# 4__Connectors___IO.net
KiCad netlist of a schematic drawn in Altium Designer
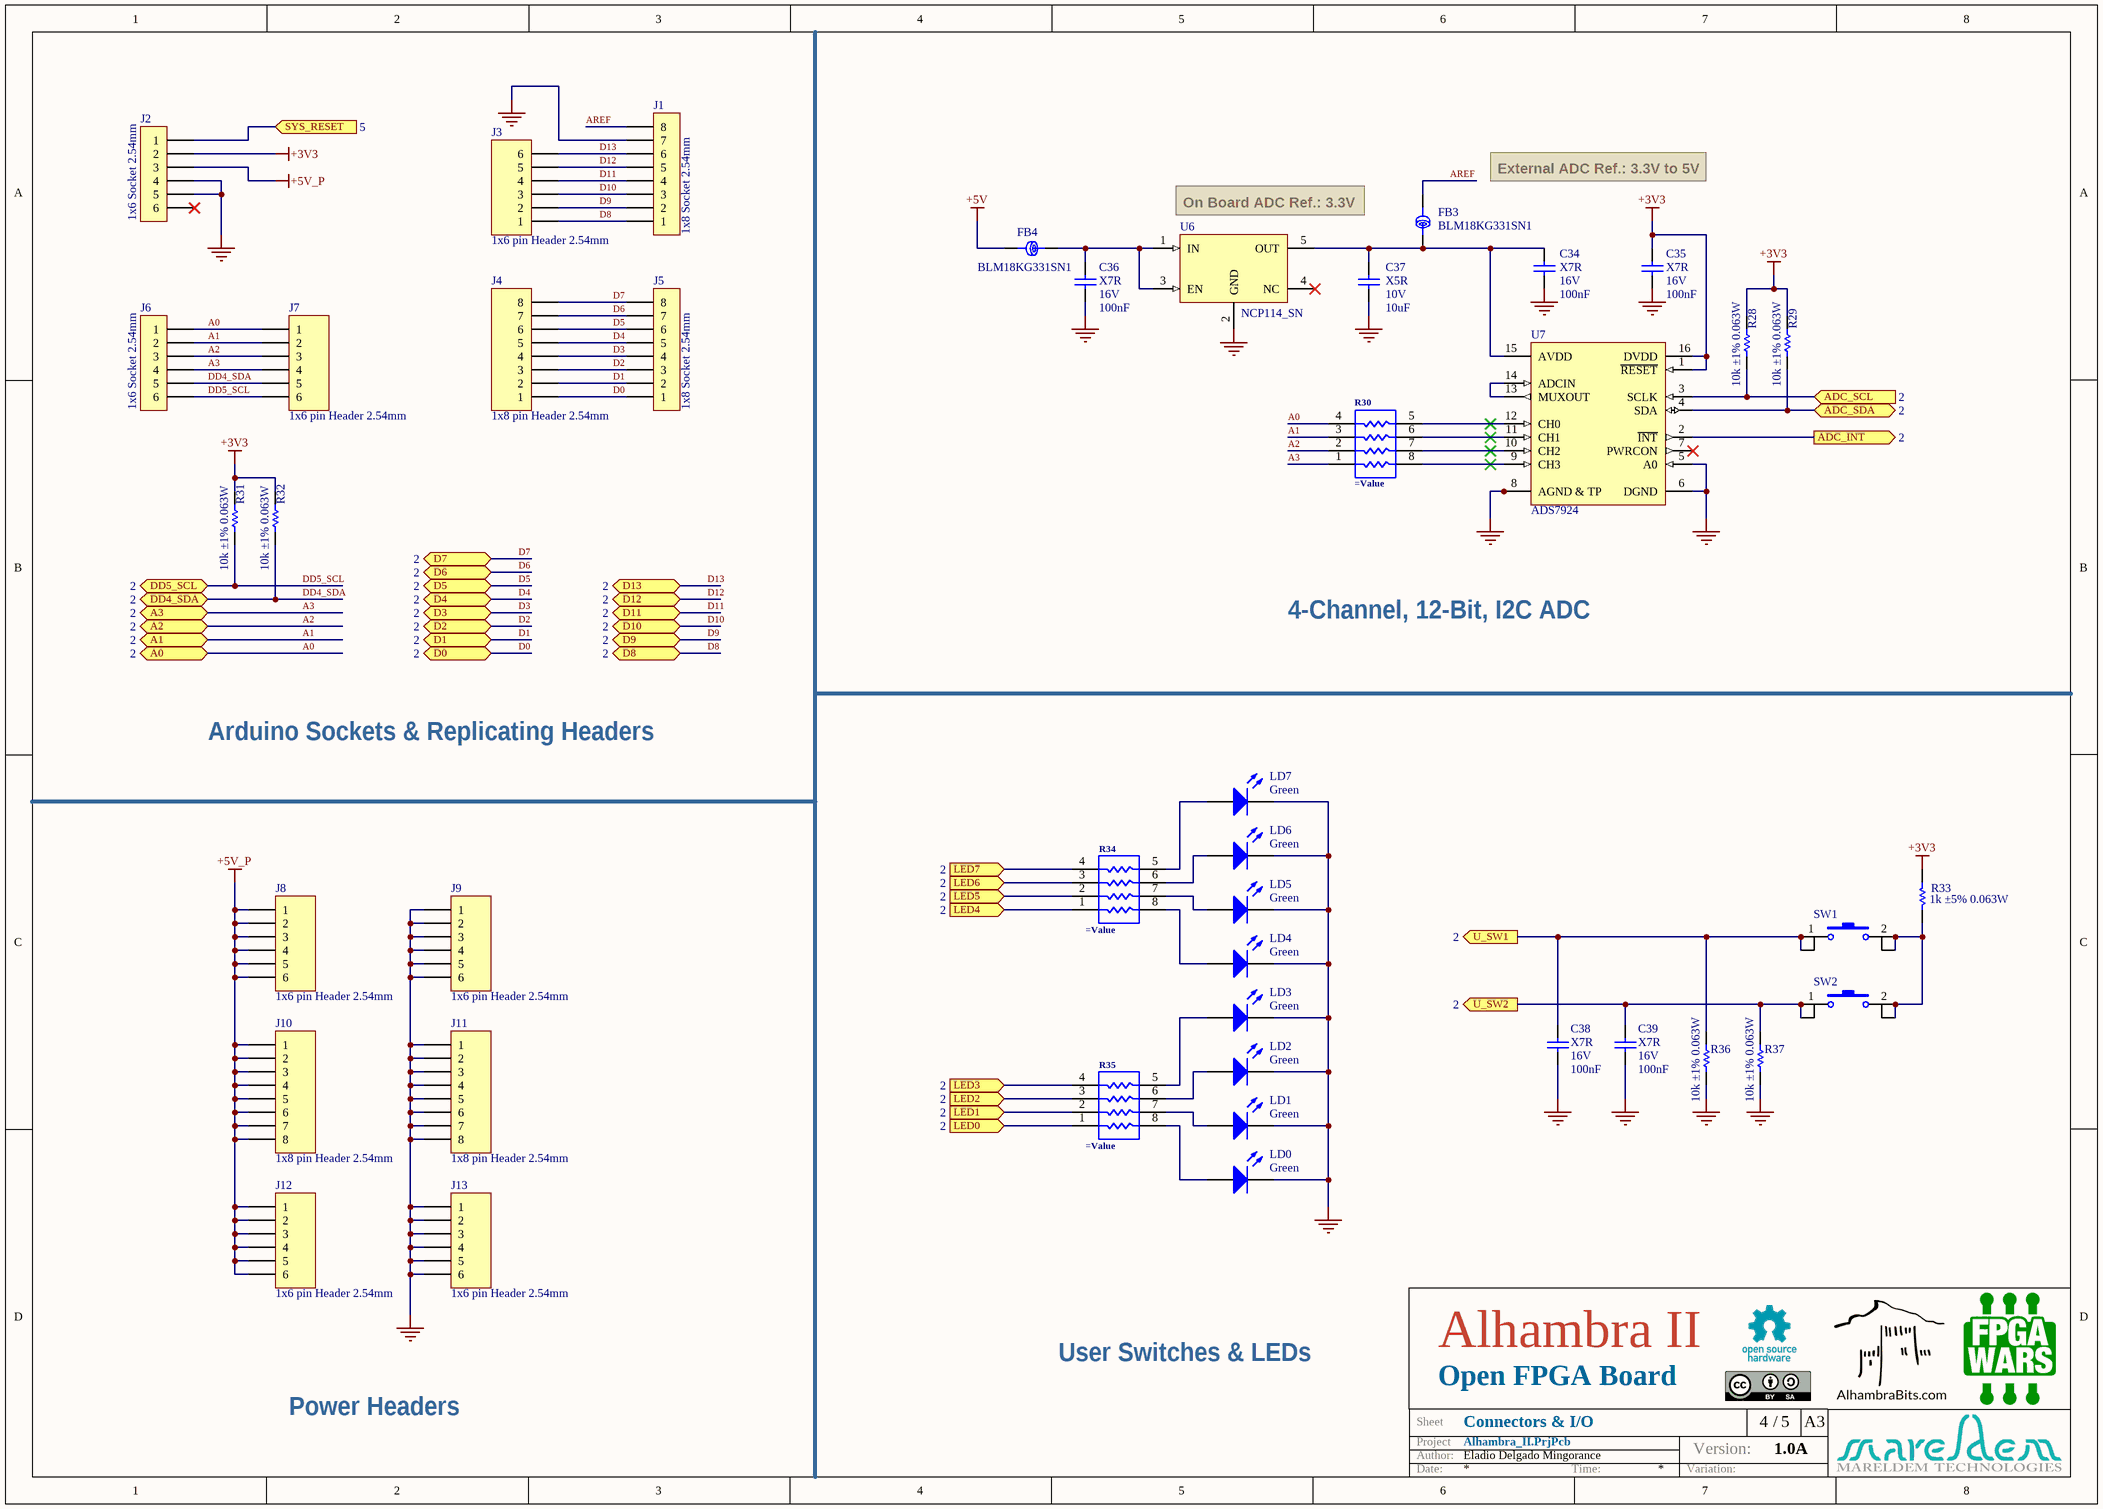
[diagram p0: [4]_Connectors_&_IO.SchDoc]

(export (version "E")
  (design (tool "Eeschema 10.0.6"))
  (components
    (comp (ref "C34")
      (value "Capacitor")
      (footprint "C0402")
      (description "Capacitor SMD")
      (fields
        (field (name "DIELECTRIC") "X7R")
        (field (name "VOLTAGE") "16V")
        (field (name "CAPACITANCE") "100nF")
        (field (name "PART NUMBER") "C0402_100nF_16V_±10%")
        (field (name "TOLERANCE") "±10%")
      )
      (libsource (lib "") (part "Capacitor_1"))
    )
    (comp (ref "C35")
      (value "Capacitor")
      (footprint "C0402")
      (description "Capacitor SMD")
      (fields
        (field (name "DIELECTRIC") "X7R")
        (field (name "VOLTAGE") "16V")
        (field (name "CAPACITANCE") "100nF")
        (field (name "PART NUMBER") "C0402_100nF_16V_±10%")
        (field (name "TOLERANCE") "±10%")
      )
      (libsource (lib "") (part "Capacitor_1"))
    )
    (comp (ref "C36")
      (value "Capacitor")
      (footprint "C0402")
      (description "Capacitor SMD")
      (fields
        (field (name "DIELECTRIC") "X7R")
        (field (name "VOLTAGE") "16V")
        (field (name "CAPACITANCE") "100nF")
        (field (name "PART NUMBER") "C0402_100nF_16V_±10%")
        (field (name "TOLERANCE") "±10%")
      )
      (libsource (lib "") (part "Capacitor_1"))
    )
    (comp (ref "C37")
      (value "Capacitor")
      (footprint "C0603")
      (description "Capacitor SMD")
      (fields
        (field (name "DIELECTRIC") "X5R")
        (field (name "VOLTAGE") "10V")
        (field (name "CAPACITANCE") "10uF")
        (field (name "PART NUMBER") "C0603_10uF_10V_±10%")
        (field (name "TOLERANCE") "±10%")
      )
      (libsource (lib "Pasives_Capacitor_SMD") (part "Capacitor"))
    )
    (comp (ref "C38")
      (value "Capacitor")
      (footprint "C0402")
      (description "Capacitor SMD")
      (fields
        (field (name "DIELECTRIC") "X7R")
        (field (name "VOLTAGE") "16V")
        (field (name "CAPACITANCE") "100nF")
        (field (name "PART NUMBER") "C0402_100nF_16V_±10%")
        (field (name "TOLERANCE") "±10%")
      )
      (libsource (lib "") (part "Capacitor_1"))
    )
    (comp (ref "C39")
      (value "Capacitor")
      (footprint "C0402")
      (description "Capacitor SMD")
      (fields
        (field (name "DIELECTRIC") "X7R")
        (field (name "VOLTAGE") "16V")
        (field (name "CAPACITANCE") "100nF")
        (field (name "PART NUMBER") "C0402_100nF_16V_±10%")
        (field (name "TOLERANCE") "±10%")
      )
      (libsource (lib "") (part "Capacitor_1"))
    )
    (comp (ref "FB3")
      (value "BLM18KG331SN1")
      (footprint "L0603")
      (description "Ferrite Bead")
      (fields (field (name "PART NUMBER") "L0603_330R_0,080R_1700 mA") (field (name "MANUFACTURER") "Murata"))
      (libsource (lib "") (part "Ferrite Bead_1"))
    )
    (comp (ref "FB4")
      (value "BLM18KG331SN1")
      (footprint "L0603")
      (description "Ferrite Bead")
      (fields (field (name "PART NUMBER") "L0603_330R_0,080R_1700 mA") (field (name "MANUFACTURER") "Murata"))
      (libsource (lib "Pasives_Inductor_SMD") (part "Ferrite Bead"))
    )
    (comp (ref "J1")
      (value "1x8 Socket 2.54mm")
      (footprint "1x8 Socket Header THT 2.54mm PIH")
      (description "Connector, 8 pin Socket Header 2.54mm")
      (fields (field (name "MANUFACTURER") "Samtec") (field (name "PART NUMBER") "CON_SH_THT2.54_8 PIH"))
      (libsource (lib "Connector_SocketHeader_2.54") (part "1x8 Socket Header 2.54mm"))
    )
    (comp (ref "J2")
      (value "1x6 Socket 2.54mm")
      (footprint "1x6 Socket Header THT 2.54mm PIH")
      (description "Connector, 6 pin Socket Header 2.54mm")
      (fields (field (name "MANUFACTURER") "Samtec") (field (name "PART NUMBER") "CON_SH_THT2.54_6 PIH"))
      (libsource (lib "Connector_SocketHeader_2.54") (part "1x6 Socket Header 2.54mm"))
    )
    (comp (ref "J3")
      (value "1x6 pin Header 2.54mm")
      (footprint "1x6 Pin Header 2.54 WHITE PIH")
      (description "Connector, 1x6 pin Header 2.54mm")
      (fields
        (field (name "MANUFACTURER") "Samtec")
        (field (name "PART NUMBER") "CON_PH_THT2.54_6 Natural PIH")
      )
      (libsource (lib "") (part "1x6 pin Header 2.54mm_1"))
    )
    (comp (ref "J4")
      (value "1x8 pin Header 2.54mm")
      (footprint "1x8 Pin Header 2.54 WHITE PIH")
      (description "Connector, 1x8 pin Header 2.54mm")
      (fields
        (field (name "MANUFACTURER") "Samtec")
        (field (name "PART NUMBER") "CON_PH_THT2.54_8 Natural PIH")
      )
      (libsource (lib "") (part "1x8 pin Header 2.54mm_1"))
    )
    (comp (ref "J5")
      (value "1x8 Socket 2.54mm")
      (footprint "1x8 Socket Header THT 2.54mm PIH")
      (description "Connector, 8 pin Socket Header 2.54mm")
      (fields (field (name "MANUFACTURER") "Samtec") (field (name "PART NUMBER") "CON_SH_THT2.54_8 PIH"))
      (libsource (lib "Connector_SocketHeader_2.54") (part "1x8 Socket Header 2.54mm"))
    )
    (comp (ref "J6")
      (value "1x6 Socket 2.54mm")
      (footprint "1x6 Socket Header THT 2.54mm PIH")
      (description "Connector, 6 pin Socket Header 2.54mm")
      (fields (field (name "MANUFACTURER") "Samtec") (field (name "PART NUMBER") "CON_SH_THT2.54_6 PIH"))
      (libsource (lib "Connector_SocketHeader_2.54") (part "1x6 Socket Header 2.54mm"))
    )
    (comp (ref "J7")
      (value "1x6 pin Header 2.54mm")
      (footprint "1x6 Pin Header 2.54 WHITE PIH")
      (description "Connector, 1x6 pin Header 2.54mm")
      (fields
        (field (name "MANUFACTURER") "Samtec")
        (field (name "PART NUMBER") "CON_PH_THT2.54_6 Natural PIH")
      )
      (libsource (lib "Connector_PinHeader_2.54") (part "1x6 pin Header 2.54mm"))
    )
    (comp (ref "J8")
      (value "1x6 pin Header 2.54mm")
      (footprint "1x6 Pin Header 2.54 RED PIH")
      (description "Connector, 1x6 pin Header 2.54mm")
      (fields (field (name "MANUFACTURER") "Samtec") (field (name "PART NUMBER") "CON_PH_THT2.54_6 Red PIH"))
      (libsource (lib "Connector_PinHeader_2.54") (part "1x6 pin Header 2.54mm"))
    )
    (comp (ref "J9")
      (value "1x6 pin Header 2.54mm")
      (footprint "1x6 Pin Header 2.54 BLACK PIH")
      (description "Connector, 1x6 pin Header 2.54mm")
      (fields
        (field (name "MANUFACTURER") "Samtec")
        (field (name "PART NUMBER") "CON_PH_THT2.54_6 Black PIH")
      )
      (libsource (lib "Connector_PinHeader_2.54") (part "1x6 pin Header 2.54mm"))
    )
    (comp (ref "J10")
      (value "1x8 pin Header 2.54mm")
      (footprint "1x8 Pin Header 2.54 RED PIH")
      (description "Connector, 1x8 pin Header 2.54mm")
      (fields (field (name "MANUFACTURER") "Samtec") (field (name "PART NUMBER") "CON_PH_THT2.54_8 Red PIH"))
      (libsource (lib "Connector_PinHeader_2.54") (part "1x8 pin Header 2.54mm"))
    )
    (comp (ref "J11")
      (value "1x8 pin Header 2.54mm")
      (footprint "1x8 Pin Header 2.54 BLACK PIH")
      (description "Connector, 1x8 pin Header 2.54mm")
      (fields
        (field (name "MANUFACTURER") "Samtec")
        (field (name "PART NUMBER") "CON_PH_THT2.54_8 Black PIH")
      )
      (libsource (lib "Connector_PinHeader_2.54") (part "1x8 pin Header 2.54mm"))
    )
    (comp (ref "J12")
      (value "1x6 pin Header 2.54mm")
      (footprint "1x6 Pin Header 2.54 RED PIH")
      (description "Connector, 1x6 pin Header 2.54mm")
      (fields (field (name "MANUFACTURER") "Samtec") (field (name "PART NUMBER") "CON_PH_THT2.54_6 Red PIH"))
      (libsource (lib "Connector_PinHeader_2.54") (part "1x6 pin Header 2.54mm"))
    )
    (comp (ref "J13")
      (value "1x6 pin Header 2.54mm")
      (footprint "1x6 Pin Header 2.54 BLACK PIH")
      (description "Connector, 1x6 pin Header 2.54mm")
      (fields
        (field (name "MANUFACTURER") "Samtec")
        (field (name "PART NUMBER") "CON_PH_THT2.54_6 Black PIH")
      )
      (libsource (lib "Connector_PinHeader_2.54") (part "1x6 pin Header 2.54mm"))
    )
    (comp (ref "LD0")
      (value "Green")
      (footprint "LED0603")
      (description "LED")
      (fields (field (name "PART NUMBER") "LED Green 0603 Wurth") (field (name "MANUFACTURER") "WE"))
      (libsource (lib "Optoelectronics") (part "LED"))
    )
    (comp (ref "LD1")
      (value "Green")
      (footprint "LED0603")
      (description "LED")
      (fields (field (name "PART NUMBER") "LED Green 0603 Wurth") (field (name "MANUFACTURER") "WE"))
      (libsource (lib "Optoelectronics") (part "LED"))
    )
    (comp (ref "LD2")
      (value "Green")
      (footprint "LED0603")
      (description "LED")
      (fields (field (name "PART NUMBER") "LED Green 0603 Wurth") (field (name "MANUFACTURER") "WE"))
      (libsource (lib "Optoelectronics") (part "LED"))
    )
    (comp (ref "LD3")
      (value "Green")
      (footprint "LED0603")
      (description "LED")
      (fields (field (name "PART NUMBER") "LED Green 0603 Wurth") (field (name "MANUFACTURER") "WE"))
      (libsource (lib "Optoelectronics") (part "LED"))
    )
    (comp (ref "LD4")
      (value "Green")
      (footprint "LED0603")
      (description "LED")
      (fields (field (name "PART NUMBER") "LED Green 0603 Wurth") (field (name "MANUFACTURER") "WE"))
      (libsource (lib "Optoelectronics") (part "LED"))
    )
    (comp (ref "LD5")
      (value "Green")
      (footprint "LED0603")
      (description "LED")
      (fields (field (name "PART NUMBER") "LED Green 0603 Wurth") (field (name "MANUFACTURER") "WE"))
      (libsource (lib "Optoelectronics") (part "LED"))
    )
    (comp (ref "LD6")
      (value "Green")
      (footprint "LED0603")
      (description "LED")
      (fields (field (name "PART NUMBER") "LED Green 0603 Wurth") (field (name "MANUFACTURER") "WE"))
      (libsource (lib "Optoelectronics") (part "LED"))
    )
    (comp (ref "LD7")
      (value "Green")
      (footprint "LED0603")
      (description "LED")
      (fields (field (name "PART NUMBER") "LED Green 0603 Wurth") (field (name "MANUFACTURER") "WE"))
      (libsource (lib "Optoelectronics") (part "LED"))
    )
    (comp (ref "R28")
      (value "10k ±1% 0.063W")
      (footprint "R0402")
      (description "Resistor, SMD")
      (fields (field (name "TOLERANCE") "±1%") (field (name "POWER") "0.063W"))
      (libsource (lib "Pasives_Resistor_SMD") (part "Resistor"))
    )
    (comp (ref "R29")
      (value "10k ±1% 0.063W")
      (footprint "R0402")
      (description "Resistor, SMD")
      (fields (field (name "TOLERANCE") "±1%") (field (name "POWER") "0.063W"))
      (libsource (lib "Pasives_Resistor_SMD") (part "Resistor"))
    )
    (comp (ref "R30")
      (value "~")
      (footprint "4xArray_1206_Convex")
      (description "Resistor, Array 4x1")
      (fields
        (field (name "PART NUMBER") "4xArray_1206_Convex_100R_0,0625W_±5%")
        (field (name "POWER") "0,0625W")
      )
      (libsource (lib "Pasives_Resistor_SMD") (part "Resistor_4x"))
    )
    (comp (ref "R31")
      (value "10k ±1% 0.063W")
      (footprint "R0402")
      (description "Resistor, SMD")
      (fields (field (name "TOLERANCE") "±1%") (field (name "POWER") "0.063W"))
      (libsource (lib "Pasives_Resistor_SMD") (part "Resistor"))
    )
    (comp (ref "R32")
      (value "10k ±1% 0.063W")
      (footprint "R0402")
      (description "Resistor, SMD")
      (fields (field (name "TOLERANCE") "±1%") (field (name "POWER") "0.063W"))
      (libsource (lib "Pasives_Resistor_SMD") (part "Resistor"))
    )
    (comp (ref "R33")
      (value "1k ±5% 0.063W")
      (footprint "R0402")
      (description "Resistor, SMD")
      (fields (field (name "TOLERANCE") "±5%") (field (name "POWER") "0.063W"))
      (libsource (lib "Pasives_Resistor_SMD") (part "Resistor"))
    )
    (comp (ref "R34")
      (value "~")
      (footprint "4xArray_1206_Convex")
      (description "Resistor, Array 4x1")
      (fields
        (field (name "PART NUMBER") "4xArray_1206_Convex_470R_0,0625W_0,05")
        (field (name "POWER") "0,0625W")
      )
      (libsource (lib "Pasives_Resistor_SMD") (part "Resistor_4x"))
    )
    (comp (ref "R35")
      (value "~")
      (footprint "4xArray_1206_Convex")
      (description "Resistor, Array 4x1")
      (fields
        (field (name "PART NUMBER") "4xArray_1206_Convex_470R_0,0625W_0,05")
        (field (name "POWER") "0,0625W")
      )
      (libsource (lib "Pasives_Resistor_SMD") (part "Resistor_4x"))
    )
    (comp (ref "R36")
      (value "10k ±1% 0.063W")
      (footprint "R0402")
      (description "Resistor, SMD")
      (fields (field (name "TOLERANCE") "±1%") (field (name "POWER") "0.063W"))
      (libsource (lib "Pasives_Resistor_SMD") (part "Resistor"))
    )
    (comp (ref "R37")
      (value "10k ±1% 0.063W")
      (footprint "R0402")
      (description "Resistor, SMD")
      (fields (field (name "TOLERANCE") "±1%") (field (name "POWER") "0.063W"))
      (libsource (lib "Pasives_Resistor_SMD") (part "Resistor"))
    )
    (comp (ref "SW1")
      (value "Switch_4P_SP_1-3_4-2")
      (footprint "4363x30458xx")
      (description "Micro miniature pushbutton surface Switch")
      (fields (field (name "PART NUMBER") "SW 4,7x3,5 mm SMD side push") (field (name "MANUFACTURER") "WE"))
      (libsource (lib "Electromechanical") (part "Switch_4P_SP_1-3_4-2"))
    )
    (comp (ref "SW2")
      (value "Switch_4P_SP_1-3_4-2")
      (footprint "4363x30458xx")
      (description "Micro miniature pushbutton surface Switch")
      (fields (field (name "PART NUMBER") "SW 4,7x3,5 mm SMD side push") (field (name "MANUFACTURER") "WE"))
      (libsource (lib "Electromechanical") (part "Switch_4P_SP_1-3_4-2"))
    )
    (comp (ref "U6")
      (value "NCP114_SN")
      (footprint "SOT23-5_M")
      (description "LDO Regulator, 5pin, SOT-23")
      (fields (field (name "PART NUMBER") "NCP114") (field (name "MANUFACTURER") "ON Semiconductor"))
      (libsource (lib "Power_Regulator") (part "NCP114_SN"))
    )
    (comp (ref "U7")
      (value "ADS7924")
      (footprint "QFN16")
      (description "ADC Converter, 12-Bit, 4-Ch, I2C")
      (fields (field (name "MANUFACTURER") "Texas Instruments"))
      (libsource (lib "Data_Converters") (part "ADS7924"))
    )
  )
  (nets
    (net (code "1") (name "+3V3") (class "Default")
      (node (ref "C35") (pin "2") (pinfunction "2_2") (pintype "passive"))
      (node (ref "J2") (pin "2") (pinfunction "2_2") (pintype "passive"))
      (node (ref "R28") (pin "2") (pinfunction "2_2") (pintype "passive"))
      (node (ref "R29") (pin "2") (pinfunction "2_2") (pintype "passive"))
      (node (ref "R31") (pin "2") (pinfunction "2_2") (pintype "passive"))
      (node (ref "R32") (pin "2") (pinfunction "2_2") (pintype "passive"))
      (node (ref "R33") (pin "1") (pinfunction "1_1") (pintype "passive"))
      (node (ref "U7") (pin "1") (pinfunction "RESET_1") (pintype "input"))
      (node (ref "U7") (pin "16") (pinfunction "DVDD_16") (pintype "power_in"))
    )
    (net (code "2") (name "+5V") (class "Default")
      (node (ref "FB4") (pin "2") (pinfunction "2_2") (pintype "passive"))
    )
    (net (code "3") (name "+5V_P") (class "Default")
      (node (ref "J10") (pin "1") (pinfunction "1_1") (pintype "passive"))
      (node (ref "J10") (pin "2") (pinfunction "2_2") (pintype "passive"))
      (node (ref "J10") (pin "3") (pinfunction "3_3") (pintype "passive"))
      (node (ref "J10") (pin "4") (pinfunction "4_4") (pintype "passive"))
      (node (ref "J10") (pin "5") (pinfunction "5_5") (pintype "passive"))
      (node (ref "J10") (pin "6") (pinfunction "6_6") (pintype "passive"))
      (node (ref "J10") (pin "7") (pinfunction "7_7") (pintype "passive"))
      (node (ref "J10") (pin "8") (pinfunction "8_8") (pintype "passive"))
      (node (ref "J12") (pin "1") (pinfunction "1_1") (pintype "passive"))
      (node (ref "J12") (pin "2") (pinfunction "2_2") (pintype "passive"))
      (node (ref "J12") (pin "3") (pinfunction "3_3") (pintype "passive"))
      (node (ref "J12") (pin "4") (pinfunction "4_4") (pintype "passive"))
      (node (ref "J12") (pin "5") (pinfunction "5_5") (pintype "passive"))
      (node (ref "J12") (pin "6") (pinfunction "6_6") (pintype "passive"))
      (node (ref "J2") (pin "3") (pinfunction "3_3") (pintype "passive"))
      (node (ref "J8") (pin "1") (pinfunction "1_1") (pintype "passive"))
      (node (ref "J8") (pin "2") (pinfunction "2_2") (pintype "passive"))
      (node (ref "J8") (pin "3") (pinfunction "3_3") (pintype "passive"))
      (node (ref "J8") (pin "4") (pinfunction "4_4") (pintype "passive"))
      (node (ref "J8") (pin "5") (pinfunction "5_5") (pintype "passive"))
      (node (ref "J8") (pin "6") (pinfunction "6_6") (pintype "passive"))
    )
    (net (code "4") (name "/A0") (class "Default")
      (node (ref "J6") (pin "1") (pinfunction "1_1") (pintype "passive"))
      (node (ref "J7") (pin "1") (pinfunction "1_1") (pintype "passive"))
      (node (ref "R30") (pin "4") (pinfunction "4_4") (pintype "passive"))
    )
    (net (code "5") (name "/A1") (class "Default")
      (node (ref "J6") (pin "2") (pinfunction "2_2") (pintype "passive"))
      (node (ref "J7") (pin "2") (pinfunction "2_2") (pintype "passive"))
      (node (ref "R30") (pin "3") (pinfunction "3_3") (pintype "passive"))
    )
    (net (code "6") (name "/A2") (class "Default")
      (node (ref "J6") (pin "3") (pinfunction "3_3") (pintype "passive"))
      (node (ref "J7") (pin "3") (pinfunction "3_3") (pintype "passive"))
      (node (ref "R30") (pin "2") (pinfunction "2_2") (pintype "passive"))
    )
    (net (code "7") (name "/A3") (class "Default")
      (node (ref "J6") (pin "4") (pinfunction "4_4") (pintype "passive"))
      (node (ref "J7") (pin "4") (pinfunction "4_4") (pintype "passive"))
      (node (ref "R30") (pin "1") (pinfunction "1_1") (pintype "passive"))
    )
    (net (code "8") (name "/ADC_INT") (class "Default")
      (node (ref "U7") (pin "2") (pinfunction "INT_2") (pintype "output"))
    )
    (net (code "9") (name "/ADC_SCL") (class "Default")
      (node (ref "R28") (pin "1") (pinfunction "1_1") (pintype "passive"))
      (node (ref "U7") (pin "3") (pinfunction "SCLK_3") (pintype "input"))
    )
    (net (code "10") (name "/ADC_SDA") (class "Default")
      (node (ref "R29") (pin "1") (pinfunction "1_1") (pintype "passive"))
      (node (ref "U7") (pin "4") (pinfunction "SDA_4") (pintype "bidirectional"))
    )
    (net (code "11") (name "/AREF") (class "Default")
      (node (ref "FB3") (pin "2") (pinfunction "2_2") (pintype "passive"))
      (node (ref "J1") (pin "8") (pinfunction "8_8") (pintype "passive"))
    )
    (net (code "12") (name "/D0") (class "Default")
      (node (ref "J4") (pin "1") (pinfunction "1_1") (pintype "passive"))
      (node (ref "J5") (pin "1") (pinfunction "1_1") (pintype "passive"))
    )
    (net (code "13") (name "/D1") (class "Default")
      (node (ref "J4") (pin "2") (pinfunction "2_2") (pintype "passive"))
      (node (ref "J5") (pin "2") (pinfunction "2_2") (pintype "passive"))
    )
    (net (code "14") (name "/D2") (class "Default")
      (node (ref "J4") (pin "3") (pinfunction "3_3") (pintype "passive"))
      (node (ref "J5") (pin "3") (pinfunction "3_3") (pintype "passive"))
    )
    (net (code "15") (name "/D3") (class "Default")
      (node (ref "J4") (pin "4") (pinfunction "4_4") (pintype "passive"))
      (node (ref "J5") (pin "4") (pinfunction "4_4") (pintype "passive"))
    )
    (net (code "16") (name "/D4") (class "Default")
      (node (ref "J4") (pin "5") (pinfunction "5_5") (pintype "passive"))
      (node (ref "J5") (pin "5") (pinfunction "5_5") (pintype "passive"))
    )
    (net (code "17") (name "/D5") (class "Default")
      (node (ref "J4") (pin "6") (pinfunction "6_6") (pintype "passive"))
      (node (ref "J5") (pin "6") (pinfunction "6_6") (pintype "passive"))
    )
    (net (code "18") (name "/D6") (class "Default")
      (node (ref "J4") (pin "7") (pinfunction "7_7") (pintype "passive"))
      (node (ref "J5") (pin "7") (pinfunction "7_7") (pintype "passive"))
    )
    (net (code "19") (name "/D7") (class "Default")
      (node (ref "J4") (pin "8") (pinfunction "8_8") (pintype "passive"))
      (node (ref "J5") (pin "8") (pinfunction "8_8") (pintype "passive"))
    )
    (net (code "20") (name "/D8") (class "Default")
      (node (ref "J1") (pin "1") (pinfunction "1_1") (pintype "passive"))
      (node (ref "J3") (pin "1") (pinfunction "1_1") (pintype "passive"))
    )
    (net (code "21") (name "/D9") (class "Default")
      (node (ref "J1") (pin "2") (pinfunction "2_2") (pintype "passive"))
      (node (ref "J3") (pin "2") (pinfunction "2_2") (pintype "passive"))
    )
    (net (code "22") (name "/D10") (class "Default")
      (node (ref "J1") (pin "3") (pinfunction "3_3") (pintype "passive"))
      (node (ref "J3") (pin "3") (pinfunction "3_3") (pintype "passive"))
    )
    (net (code "23") (name "/D11") (class "Default")
      (node (ref "J1") (pin "4") (pinfunction "4_4") (pintype "passive"))
      (node (ref "J3") (pin "4") (pinfunction "4_4") (pintype "passive"))
    )
    (net (code "24") (name "/D12") (class "Default")
      (node (ref "J1") (pin "5") (pinfunction "5_5") (pintype "passive"))
      (node (ref "J3") (pin "5") (pinfunction "5_5") (pintype "passive"))
    )
    (net (code "25") (name "/D13") (class "Default")
      (node (ref "J1") (pin "6") (pinfunction "6_6") (pintype "passive"))
      (node (ref "J3") (pin "6") (pinfunction "6_6") (pintype "passive"))
    )
    (net (code "26") (name "/DD4_SDA") (class "Default")
      (node (ref "J6") (pin "5") (pinfunction "5_5") (pintype "passive"))
      (node (ref "J7") (pin "5") (pinfunction "5_5") (pintype "passive"))
      (node (ref "R32") (pin "1") (pinfunction "1_1") (pintype "passive"))
    )
    (net (code "27") (name "/DD5_SCL") (class "Default")
      (node (ref "J6") (pin "6") (pinfunction "6_6") (pintype "passive"))
      (node (ref "J7") (pin "6") (pinfunction "6_6") (pintype "passive"))
      (node (ref "R31") (pin "1") (pinfunction "1_1") (pintype "passive"))
    )
    (net (code "28") (name "/LED0") (class "Default")
      (node (ref "R35") (pin "1") (pinfunction "1_1") (pintype "passive"))
    )
    (net (code "29") (name "/LED1") (class "Default")
      (node (ref "R35") (pin "2") (pinfunction "2_2") (pintype "passive"))
    )
    (net (code "30") (name "/LED2") (class "Default")
      (node (ref "R35") (pin "3") (pinfunction "3_3") (pintype "passive"))
    )
    (net (code "31") (name "/LED3") (class "Default")
      (node (ref "R35") (pin "4") (pinfunction "4_4") (pintype "passive"))
    )
    (net (code "32") (name "/LED4") (class "Default")
      (node (ref "R34") (pin "1") (pinfunction "1_1") (pintype "passive"))
    )
    (net (code "33") (name "/LED5") (class "Default")
      (node (ref "R34") (pin "2") (pinfunction "2_2") (pintype "passive"))
    )
    (net (code "34") (name "/LED6") (class "Default")
      (node (ref "R34") (pin "3") (pinfunction "3_3") (pintype "passive"))
    )
    (net (code "35") (name "/LED7") (class "Default")
      (node (ref "R34") (pin "4") (pinfunction "4_4") (pintype "passive"))
    )
    (net (code "36") (name "/SYS_RESET") (class "Default")
      (node (ref "J2") (pin "1") (pinfunction "1_1") (pintype "passive"))
    )
    (net (code "37") (name "/U_SW1") (class "Default")
      (node (ref "C38") (pin "2") (pinfunction "2_2") (pintype "passive"))
      (node (ref "R36") (pin "2") (pinfunction "2_2") (pintype "passive"))
      (node (ref "SW1") (pin "1") (pinfunction "1_1") (pintype "passive"))
      (node (ref "SW1") (pin "3") (pinfunction "3_3") (pintype "passive"))
    )
    (net (code "38") (name "/U_SW2") (class "Default")
      (node (ref "C39") (pin "2") (pinfunction "2_2") (pintype "passive"))
      (node (ref "R37") (pin "2") (pinfunction "2_2") (pintype "passive"))
      (node (ref "SW2") (pin "1") (pinfunction "1_1") (pintype "passive"))
      (node (ref "SW2") (pin "3") (pinfunction "3_3") (pintype "passive"))
    )
    (net (code "39") (name "GND") (class "Default")
      (node (ref "C34") (pin "2") (pinfunction "2_2") (pintype "passive"))
      (node (ref "C35") (pin "1") (pinfunction "1_1") (pintype "passive"))
      (node (ref "C36") (pin "1") (pinfunction "1_1") (pintype "passive"))
      (node (ref "C37") (pin "2") (pinfunction "2_2") (pintype "passive"))
      (node (ref "C38") (pin "1") (pinfunction "1_1") (pintype "passive"))
      (node (ref "C39") (pin "1") (pinfunction "1_1") (pintype "passive"))
      (node (ref "J1") (pin "7") (pinfunction "7_7") (pintype "passive"))
      (node (ref "J11") (pin "1") (pinfunction "1_1") (pintype "passive"))
      (node (ref "J11") (pin "2") (pinfunction "2_2") (pintype "passive"))
      (node (ref "J11") (pin "3") (pinfunction "3_3") (pintype "passive"))
      (node (ref "J11") (pin "4") (pinfunction "4_4") (pintype "passive"))
      (node (ref "J11") (pin "5") (pinfunction "5_5") (pintype "passive"))
      (node (ref "J11") (pin "6") (pinfunction "6_6") (pintype "passive"))
      (node (ref "J11") (pin "7") (pinfunction "7_7") (pintype "passive"))
      (node (ref "J11") (pin "8") (pinfunction "8_8") (pintype "passive"))
      (node (ref "J13") (pin "1") (pinfunction "1_1") (pintype "passive"))
      (node (ref "J13") (pin "2") (pinfunction "2_2") (pintype "passive"))
      (node (ref "J13") (pin "3") (pinfunction "3_3") (pintype "passive"))
      (node (ref "J13") (pin "4") (pinfunction "4_4") (pintype "passive"))
      (node (ref "J13") (pin "5") (pinfunction "5_5") (pintype "passive"))
      (node (ref "J13") (pin "6") (pinfunction "6_6") (pintype "passive"))
      (node (ref "J2") (pin "4") (pinfunction "4_4") (pintype "passive"))
      (node (ref "J2") (pin "5") (pinfunction "5_5") (pintype "passive"))
      (node (ref "J9") (pin "1") (pinfunction "1_1") (pintype "passive"))
      (node (ref "J9") (pin "2") (pinfunction "2_2") (pintype "passive"))
      (node (ref "J9") (pin "3") (pinfunction "3_3") (pintype "passive"))
      (node (ref "J9") (pin "4") (pinfunction "4_4") (pintype "passive"))
      (node (ref "J9") (pin "5") (pinfunction "5_5") (pintype "passive"))
      (node (ref "J9") (pin "6") (pinfunction "6_6") (pintype "passive"))
      (node (ref "LD0") (pin "K") (pinfunction "K_K") (pintype "passive"))
      (node (ref "LD1") (pin "K") (pinfunction "K_K") (pintype "passive"))
      (node (ref "LD2") (pin "K") (pinfunction "K_K") (pintype "passive"))
      (node (ref "LD3") (pin "K") (pinfunction "K_K") (pintype "passive"))
      (node (ref "LD4") (pin "K") (pinfunction "K_K") (pintype "passive"))
      (node (ref "LD5") (pin "K") (pinfunction "K_K") (pintype "passive"))
      (node (ref "LD6") (pin "K") (pinfunction "K_K") (pintype "passive"))
      (node (ref "LD7") (pin "K") (pinfunction "K_K") (pintype "passive"))
      (node (ref "R36") (pin "1") (pinfunction "1_1") (pintype "passive"))
      (node (ref "R37") (pin "1") (pinfunction "1_1") (pintype "passive"))
      (node (ref "U6") (pin "2") (pinfunction "GND_2") (pintype "power_in"))
      (node (ref "U7") (pin "0") (pinfunction "TP_0") (pintype "power_in"))
      (node (ref "U7") (pin "5") (pinfunction "A0_5") (pintype "input"))
      (node (ref "U7") (pin "6") (pinfunction "DGND_6") (pintype "power_in"))
      (node (ref "U7") (pin "8") (pinfunction "AGND_&_TP_8") (pintype "power_in"))
    )
    (net (code "40") (name "Net-(LD0-PadA)") (class "Default")
      (node (ref "LD0") (pin "A") (pinfunction "A_A") (pintype "passive"))
      (node (ref "R35") (pin "8") (pinfunction "8_8") (pintype "passive"))
    )
    (net (code "41") (name "Net-(LD1-PadA)") (class "Default")
      (node (ref "LD1") (pin "A") (pinfunction "A_A") (pintype "passive"))
      (node (ref "R35") (pin "7") (pinfunction "7_7") (pintype "passive"))
    )
    (net (code "42") (name "Net-(LD2-PadA)") (class "Default")
      (node (ref "LD2") (pin "A") (pinfunction "A_A") (pintype "passive"))
      (node (ref "R35") (pin "6") (pinfunction "6_6") (pintype "passive"))
    )
    (net (code "43") (name "Net-(LD3-PadA)") (class "Default")
      (node (ref "LD3") (pin "A") (pinfunction "A_A") (pintype "passive"))
      (node (ref "R35") (pin "5") (pinfunction "5_5") (pintype "passive"))
    )
    (net (code "44") (name "Net-(LD4-PadA)") (class "Default")
      (node (ref "LD4") (pin "A") (pinfunction "A_A") (pintype "passive"))
      (node (ref "R34") (pin "8") (pinfunction "8_8") (pintype "passive"))
    )
    (net (code "45") (name "Net-(LD5-PadA)") (class "Default")
      (node (ref "LD5") (pin "A") (pinfunction "A_A") (pintype "passive"))
      (node (ref "R34") (pin "7") (pinfunction "7_7") (pintype "passive"))
    )
    (net (code "46") (name "Net-(LD6-PadA)") (class "Default")
      (node (ref "LD6") (pin "A") (pinfunction "A_A") (pintype "passive"))
      (node (ref "R34") (pin "6") (pinfunction "6_6") (pintype "passive"))
    )
    (net (code "47") (name "Net-(LD7-PadA)") (class "Default")
      (node (ref "LD7") (pin "A") (pinfunction "A_A") (pintype "passive"))
      (node (ref "R34") (pin "5") (pinfunction "5_5") (pintype "passive"))
    )
    (net (code "48") (name "Net-(R33-Pad2)") (class "Default")
      (node (ref "R33") (pin "2") (pinfunction "2_2") (pintype "passive"))
      (node (ref "SW1") (pin "2") (pinfunction "2_2") (pintype "passive"))
      (node (ref "SW1") (pin "4") (pinfunction "4_4") (pintype "passive"))
      (node (ref "SW2") (pin "2") (pinfunction "2_2") (pintype "passive"))
      (node (ref "SW2") (pin "4") (pinfunction "4_4") (pintype "passive"))
    )
    (net (code "49") (name "Net-(U6-EN)") (class "Default")
      (node (ref "C36") (pin "2") (pinfunction "2_2") (pintype "passive"))
      (node (ref "FB4") (pin "1") (pinfunction "1_1") (pintype "passive"))
      (node (ref "U6") (pin "1") (pinfunction "IN_1") (pintype "input"))
      (node (ref "U6") (pin "3") (pinfunction "EN_3") (pintype "input"))
    )
    (net (code "50") (name "Net-(U6-OUT)") (class "Default")
      (node (ref "C34") (pin "1") (pinfunction "1_1") (pintype "passive"))
      (node (ref "C37") (pin "1") (pinfunction "1_1") (pintype "passive"))
      (node (ref "FB3") (pin "1") (pinfunction "1_1") (pintype "passive"))
      (node (ref "U6") (pin "5") (pinfunction "OUT_5") (pintype "power_in"))
      (node (ref "U7") (pin "15") (pinfunction "AVDD_15") (pintype "power_in"))
    )
    (net (code "51") (name "Net-(U7-ADCIN)") (class "Default")
      (node (ref "U7") (pin "13") (pinfunction "MUXOUT_13") (pintype "output"))
      (node (ref "U7") (pin "14") (pinfunction "ADCIN_14") (pintype "input"))
    )
    (net (code "52") (name "Net-(U7-CH0)") (class "Default")
      (node (ref "R30") (pin "5") (pinfunction "5_5") (pintype "passive"))
      (node (ref "U7") (pin "12") (pinfunction "CH0_12") (pintype "input"))
    )
    (net (code "53") (name "Net-(U7-CH1)") (class "Default")
      (node (ref "R30") (pin "6") (pinfunction "6_6") (pintype "passive"))
      (node (ref "U7") (pin "11") (pinfunction "CH1_11") (pintype "input"))
    )
    (net (code "54") (name "Net-(U7-CH2)") (class "Default")
      (node (ref "R30") (pin "7") (pinfunction "7_7") (pintype "passive"))
      (node (ref "U7") (pin "10") (pinfunction "CH2_10") (pintype "input"))
    )
    (net (code "55") (name "Net-(U7-CH3)") (class "Default")
      (node (ref "R30") (pin "8") (pinfunction "8_8") (pintype "passive"))
      (node (ref "U7") (pin "9") (pinfunction "CH3_9") (pintype "input"))
    )
    (net (code "56") (name "unconnected-(J2-Pad6)") (class "Default")
      (node (ref "J2") (pin "6") (pinfunction "6_6") (pintype "passive+no_connect"))
    )
    (net (code "57") (name "unconnected-(U6-NC-Pad4)") (class "Default")
      (node (ref "U6") (pin "4") (pinfunction "NC_4") (pintype "passive+no_connect"))
    )
    (net (code "58") (name "unconnected-(U7-PWRCON-Pad7)") (class "Default")
      (node (ref "U7") (pin "7") (pinfunction "PWRCON_7") (pintype "output+no_connect"))
    )
  )
)
